# ETL_083012_59mm.net
KiCad netlist of a schematic drawn in EAGLE
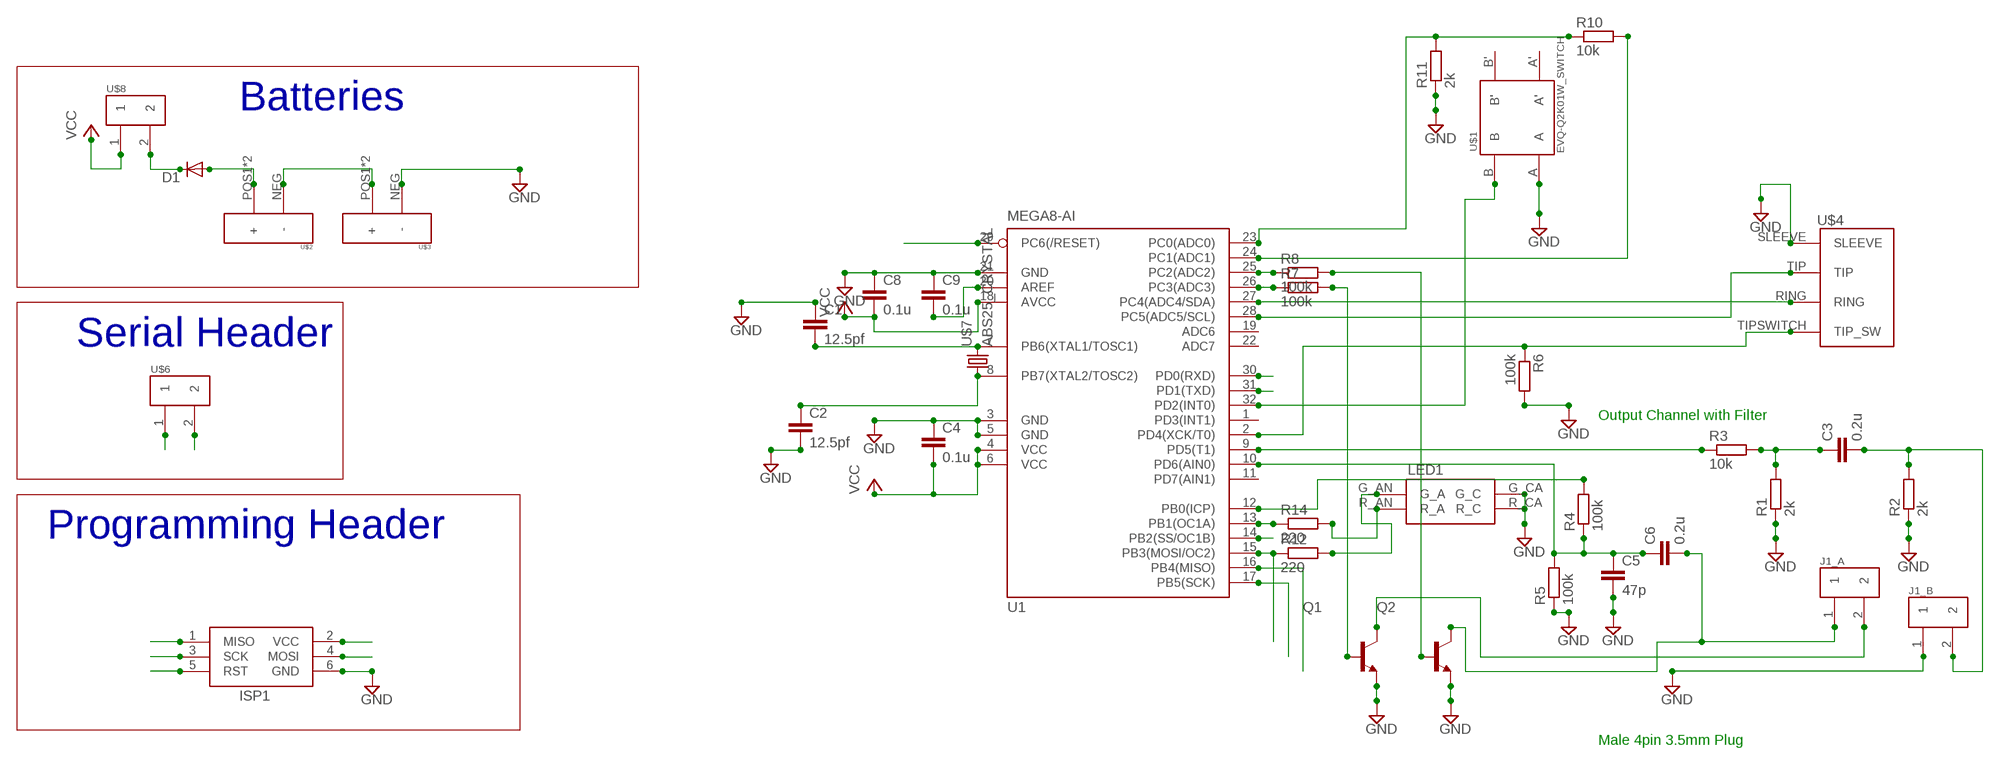
[diagram p0: schematic, sheet 1]

(export (version "E")
  (design (tool "Eeschema 10.0.6"))
  (components
    (comp (ref "C1")
      (value "12.5pf")
      (footprint "eagle-import:C0402")
      (libsource (lib "eagle-import") (part "C-EUC0402"))
    )
    (comp (ref "C2")
      (value "12.5pf")
      (footprint "eagle-import:C0402")
      (libsource (lib "eagle-import") (part "C-EUC0402"))
    )
    (comp (ref "C3")
      (value "0.2u")
      (footprint "eagle-import:C0402")
      (libsource (lib "eagle-import") (part "C-EUC0402"))
    )
    (comp (ref "C4")
      (value "0.1u")
      (footprint "eagle-import:C0402")
      (libsource (lib "eagle-import") (part "C-EUC0402"))
    )
    (comp (ref "C5")
      (value "47p")
      (footprint "eagle-import:C0402")
      (libsource (lib "eagle-import") (part "C-EUC0402"))
    )
    (comp (ref "C6")
      (value "0.2u")
      (footprint "eagle-import:C0402")
      (libsource (lib "eagle-import") (part "C-EUC0402"))
    )
    (comp (ref "C8")
      (value "0.1u")
      (footprint "eagle-import:C0402")
      (libsource (lib "eagle-import") (part "C-EUC0402"))
    )
    (comp (ref "C9")
      (value "0.1u")
      (footprint "eagle-import:C0402")
      (libsource (lib "eagle-import") (part "C-EUC0402"))
    )
    (comp (ref "D1")
      (value "DIODE-SOD323-R")
      (footprint "eagle-import:SOD323-R")
      (libsource (lib "eagle-import") (part "DIODE-SOD323-R"))
    )
    (comp (ref "ISP1")
      (value "AVRISP-6")
      (footprint "eagle-import:AVRISP")
      (libsource (lib "eagle-import") (part "AVRISP-6"))
    )
    (comp (ref "J1_A")
      (value "SERIAL_2_VERT")
      (footprint "eagle-import:SERIAL_2_VERT")
      (libsource (lib "eagle-import") (part "SERIAL_2_VERT"))
    )
    (comp (ref "J1_B")
      (value "SERIAL_2_VERT")
      (footprint "eagle-import:SERIAL_2_VERT")
      (libsource (lib "eagle-import") (part "SERIAL_2_VERT"))
    )
    (comp (ref "LED1")
      (value "LED_BI_RG")
      (footprint "eagle-import:LED_BI_1210")
      (libsource (lib "eagle-import") (part "LED_BI_RG"))
    )
    (comp (ref "Q1")
      (value "BC847-NPN-SOT23-BEC")
      (footprint "eagle-import:SOT23-BEC")
      (libsource (lib "eagle-import") (part "-NPN-SOT23-BECBC847"))
    )
    (comp (ref "Q2")
      (value "BC847-NPN-SOT23-BEC")
      (footprint "eagle-import:SOT23-BEC")
      (libsource (lib "eagle-import") (part "-NPN-SOT23-BECBC847"))
    )
    (comp (ref "R1")
      (value "2k")
      (footprint "eagle-import:R0402")
      (libsource (lib "eagle-import") (part "R-EU_R0402"))
    )
    (comp (ref "R2")
      (value "2k")
      (footprint "eagle-import:R0402")
      (libsource (lib "eagle-import") (part "R-EU_R0402"))
    )
    (comp (ref "R3")
      (value "10k")
      (footprint "eagle-import:R0402")
      (libsource (lib "eagle-import") (part "R-EU_R0402"))
    )
    (comp (ref "R4")
      (value "100k")
      (footprint "eagle-import:R0402")
      (libsource (lib "eagle-import") (part "R-EU_R0402"))
    )
    (comp (ref "R5")
      (value "100k")
      (footprint "eagle-import:R0402")
      (libsource (lib "eagle-import") (part "R-EU_R0402"))
    )
    (comp (ref "R6")
      (value "100k")
      (footprint "eagle-import:R0402")
      (libsource (lib "eagle-import") (part "R-EU_R0402"))
    )
    (comp (ref "R7")
      (value "100k")
      (footprint "eagle-import:R0402")
      (libsource (lib "eagle-import") (part "R-EU_R0402"))
    )
    (comp (ref "R8")
      (value "100k")
      (footprint "eagle-import:R0402")
      (libsource (lib "eagle-import") (part "R-EU_R0402"))
    )
    (comp (ref "R10")
      (value "10k")
      (footprint "eagle-import:R0402")
      (libsource (lib "eagle-import") (part "R-EU_R0402"))
    )
    (comp (ref "R11")
      (value "2k")
      (footprint "eagle-import:R0402")
      (libsource (lib "eagle-import") (part "R-EU_R0402"))
    )
    (comp (ref "R12")
      (value "220")
      (footprint "eagle-import:R0402")
      (libsource (lib "eagle-import") (part "R-EU_R0402"))
    )
    (comp (ref "R14")
      (value "220")
      (footprint "eagle-import:R0402")
      (libsource (lib "eagle-import") (part "R-EU_R0402"))
    )
    (comp (ref "U$1")
      (value "EVQ-Q2K01W_SWITCH")
      (footprint "eagle-import:EVQ-Q2K01W_SWITCH")
      (libsource (lib "eagle-import") (part "EVQ-Q2K01W_SWITCH"))
    )
    (comp (ref "U$2")
      (value "22M2620_BATTHOLDER")
      (footprint "eagle-import:22M2620_BATTHOLDER")
      (libsource (lib "eagle-import") (part "22M2620_BATTHOLDER"))
    )
    (comp (ref "U$3")
      (value "22M2620_BATTHOLDER")
      (footprint "eagle-import:22M2620_BATTHOLDER")
      (libsource (lib "eagle-import") (part "22M2620_BATTHOLDER"))
    )
    (comp (ref "U$4")
      (value "SJ-3524-SMT_AUDIOJACK")
      (footprint "eagle-import:SJ-3524-SMT_AUDIOJACK")
      (libsource (lib "eagle-import") (part "SJ-3524-SMT_AUDIOJACK"))
    )
    (comp (ref "U$6")
      (value "SERIAL_2_VERT")
      (footprint "eagle-import:SERIAL_2_VERT")
      (libsource (lib "eagle-import") (part "SERIAL_2_VERT"))
    )
    (comp (ref "U$7")
      (value "ABS25_CRYSTAL")
      (footprint "eagle-import:ABS25_CRYSTAL")
      (libsource (lib "eagle-import") (part "ABS25_CRYSTAL"))
    )
    (comp (ref "U$8")
      (value "SERIAL_2_VERT")
      (footprint "eagle-import:SERIAL_2_VERT")
      (libsource (lib "eagle-import") (part "SERIAL_2_VERT"))
    )
    (comp (ref "U1")
      (value "MEGA8-AI")
      (footprint "eagle-import:TQFP32-08")
      (fields (field (name "MPN") "ATMEGA8-16AU"))
      (libsource (lib "eagle-import") (part "MEGA8-AI"))
    )
  )
  (nets
    (net (code "1") (name "/MISO") (class "Default")
      (node (ref "ISP1") (pin "1") (pinfunction "MISO_1") (pintype "input"))
      (node (ref "U1") (pin "16") (pinfunction "PB4(MISO)_16") (pintype "bidirectional"))
    )
    (net (code "2") (name "/MOSI") (class "Default")
      (node (ref "ISP1") (pin "4") (pinfunction "MOSI_4") (pintype "output"))
      (node (ref "R12") (pin "1") (pinfunction "1_1") (pintype "passive"))
      (node (ref "U1") (pin "15") (pinfunction "PB3(MOSI/OC2)_15") (pintype "bidirectional"))
    )
    (net (code "3") (name "/PD0") (class "Default")
      (node (ref "U$6") (pin "1") (pinfunction "1_1") (pintype "bidirectional"))
      (node (ref "U1") (pin "30") (pinfunction "PD0(RXD)_30") (pintype "bidirectional"))
    )
    (net (code "4") (name "/PD1") (class "Default")
      (node (ref "U$6") (pin "2") (pinfunction "2_2") (pintype "bidirectional"))
      (node (ref "U1") (pin "31") (pinfunction "PD1(TXD)_31") (pintype "bidirectional"))
    )
    (net (code "5") (name "/RESET") (class "Default")
      (node (ref "ISP1") (pin "5") (pinfunction "RST_5") (pintype "output"))
      (node (ref "U1") (pin "29") (pinfunction "PC6(/RESET)_29") (pintype "bidirectional"))
    )
    (net (code "6") (name "/SCK") (class "Default")
      (node (ref "ISP1") (pin "3") (pinfunction "SCK_3") (pintype "output"))
      (node (ref "U1") (pin "17") (pinfunction "PB5(SCK)_17") (pintype "bidirectional"))
    )
    (net (code "7") (name "GND") (class "Default")
      (node (ref "C1") (pin "1") (pinfunction "1_1") (pintype "passive"))
      (node (ref "C2") (pin "2") (pinfunction "2_2") (pintype "passive"))
      (node (ref "C4") (pin "1") (pinfunction "1_1") (pintype "passive"))
      (node (ref "C5") (pin "2") (pinfunction "2_2") (pintype "passive"))
      (node (ref "C8") (pin "1") (pinfunction "1_1") (pintype "passive"))
      (node (ref "C9") (pin "1") (pinfunction "1_1") (pintype "passive"))
      (node (ref "ISP1") (pin "6") (pinfunction "GND_6") (pintype "power_in"))
      (node (ref "J1_B") (pin "1") (pinfunction "1_1") (pintype "bidirectional"))
      (node (ref "LED1") (pin "G_CA") (pinfunction "G_C_G_CA") (pintype "bidirectional"))
      (node (ref "LED1") (pin "R_CA") (pinfunction "R_C_R_CA") (pintype "bidirectional"))
      (node (ref "Q1") (pin "E") (pinfunction "E_E") (pintype "passive"))
      (node (ref "Q2") (pin "E") (pinfunction "E_E") (pintype "passive"))
      (node (ref "R1") (pin "1") (pinfunction "1_1") (pintype "passive"))
      (node (ref "R11") (pin "1") (pinfunction "1_1") (pintype "passive"))
      (node (ref "R2") (pin "1") (pinfunction "1_1") (pintype "passive"))
      (node (ref "R5") (pin "1") (pinfunction "1_1") (pintype "passive"))
      (node (ref "R6") (pin "2") (pinfunction "2_2") (pintype "passive"))
      (node (ref "U$1") (pin "A") (pinfunction "A_A") (pintype "bidirectional"))
      (node (ref "U$3") (pin "NEG") (pinfunction "-_NEG") (pintype "bidirectional"))
      (node (ref "U$4") (pin "SLEEVE") (pinfunction "SLEEVE_SLEEVE") (pintype "bidirectional"))
      (node (ref "U1") (pin "21") (pinfunction "GND_21") (pintype "power_in"))
      (node (ref "U1") (pin "3") (pinfunction "GND_3") (pintype "power_in"))
      (node (ref "U1") (pin "5") (pinfunction "GND_5") (pintype "power_in"))
    )
    (net (code "8") (name "Net-(C3-Pad1)") (class "Default")
      (node (ref "C3") (pin "1") (pinfunction "1_1") (pintype "passive"))
      (node (ref "R1") (pin "2") (pinfunction "2_2") (pintype "passive"))
      (node (ref "R3") (pin "2") (pinfunction "2_2") (pintype "passive"))
    )
    (net (code "9") (name "Net-(C3-Pad2)") (class "Default")
      (node (ref "C3") (pin "2") (pinfunction "2_2") (pintype "passive"))
      (node (ref "J1_B") (pin "2") (pinfunction "2_2") (pintype "bidirectional"))
      (node (ref "R2") (pin "2") (pinfunction "2_2") (pintype "passive"))
    )
    (net (code "10") (name "Net-(C6-Pad2)") (class "Default")
      (node (ref "C6") (pin "2") (pinfunction "2_2") (pintype "passive"))
      (node (ref "J1_A") (pin "1") (pinfunction "1_1") (pintype "bidirectional"))
      (node (ref "Q2") (pin "C") (pinfunction "C_C") (pintype "passive"))
    )
    (net (code "11") (name "Net-(D1-PadA)") (class "Default")
      (node (ref "D1") (pin "A") (pinfunction "A_A") (pintype "passive"))
      (node (ref "U$2") (pin "POS1") (pinfunction "+_POS1") (pintype "bidirectional"))
      (node (ref "U$2") (pin "POS2") (pinfunction "+_POS2") (pintype "bidirectional"))
    )
    (net (code "12") (name "Net-(D1-PadC)") (class "Default")
      (node (ref "D1") (pin "C") (pinfunction "C_C") (pintype "passive"))
      (node (ref "U$8") (pin "2") (pinfunction "2_2") (pintype "bidirectional"))
    )
    (net (code "13") (name "Net-(J1_A-Pad2)") (class "Default")
      (node (ref "J1_A") (pin "2") (pinfunction "2_2") (pintype "bidirectional"))
      (node (ref "Q1") (pin "C") (pinfunction "C_C") (pintype "passive"))
    )
    (net (code "14") (name "Net-(LED1-G_A)") (class "Default")
      (node (ref "LED1") (pin "G_AN") (pinfunction "G_A_G_AN") (pintype "bidirectional"))
      (node (ref "R12") (pin "2") (pinfunction "2_2") (pintype "passive"))
    )
    (net (code "15") (name "Net-(LED1-R_A)") (class "Default")
      (node (ref "LED1") (pin "R_AN") (pinfunction "R_A_R_AN") (pintype "bidirectional"))
      (node (ref "R14") (pin "2") (pinfunction "2_2") (pintype "passive"))
    )
    (net (code "16") (name "Net-(Q1-PadB)") (class "Default")
      (node (ref "Q1") (pin "B") (pinfunction "B_B") (pintype "passive"))
      (node (ref "R7") (pin "2") (pinfunction "2_2") (pintype "passive"))
    )
    (net (code "17") (name "Net-(Q2-PadB)") (class "Default")
      (node (ref "Q2") (pin "B") (pinfunction "B_B") (pintype "passive"))
      (node (ref "R8") (pin "2") (pinfunction "2_2") (pintype "passive"))
    )
    (net (code "18") (name "Net-(U$2--)") (class "Default")
      (node (ref "U$2") (pin "NEG") (pinfunction "-_NEG") (pintype "bidirectional"))
      (node (ref "U$3") (pin "POS1") (pinfunction "+_POS1") (pintype "bidirectional"))
      (node (ref "U$3") (pin "POS2") (pinfunction "+_POS2") (pintype "bidirectional"))
    )
    (net (code "19") (name "Net-(U$4-TIP_SW)") (class "Default")
      (node (ref "R6") (pin "1") (pinfunction "1_1") (pintype "passive"))
      (node (ref "U$4") (pin "TIPSWITCH") (pinfunction "TIP_SW_TIPSWITCH") (pintype "bidirectional"))
      (node (ref "U1") (pin "2") (pinfunction "PD4(XCK/T0)_2") (pintype "bidirectional"))
    )
    (net (code "20") (name "Net-(U$7-2)") (class "Default")
      (node (ref "C1") (pin "2") (pinfunction "2_2") (pintype "passive"))
      (node (ref "U$7") (pin "4") (pinfunction "2_4") (pintype "passive"))
      (node (ref "U1") (pin "7") (pinfunction "PB6(XTAL1/TOSC1)_7") (pintype "bidirectional"))
    )
    (net (code "21") (name "Net-(U1-AREF)") (class "Default")
      (node (ref "C9") (pin "2") (pinfunction "2_2") (pintype "passive"))
      (node (ref "U1") (pin "20") (pinfunction "AREF_20") (pintype "passive"))
    )
    (net (code "22") (name "Net-(U1-PB0(ICP))") (class "Default")
      (node (ref "R4") (pin "2") (pinfunction "2_2") (pintype "passive"))
      (node (ref "U1") (pin "12") (pinfunction "PB0(ICP)_12") (pintype "bidirectional"))
    )
    (net (code "23") (name "Net-(U1-PB1(OC1A))") (class "Default")
      (node (ref "R14") (pin "1") (pinfunction "1_1") (pintype "passive"))
      (node (ref "U1") (pin "13") (pinfunction "PB1(OC1A)_13") (pintype "bidirectional"))
    )
    (net (code "24") (name "Net-(U1-PB7(XTAL2{slash}TOSC2))") (class "Default")
      (node (ref "C2") (pin "1") (pinfunction "1_1") (pintype "passive"))
      (node (ref "U$7") (pin "1") (pinfunction "1_1") (pintype "passive"))
      (node (ref "U1") (pin "8") (pinfunction "PB7(XTAL2/TOSC2)_8") (pintype "bidirectional"))
    )
    (net (code "25") (name "Net-(U1-PC0(ADC0))") (class "Default")
      (node (ref "R10") (pin "1") (pinfunction "1_1") (pintype "passive"))
      (node (ref "R11") (pin "2") (pinfunction "2_2") (pintype "passive"))
      (node (ref "U1") (pin "23") (pinfunction "PC0(ADC0)_23") (pintype "bidirectional"))
    )
    (net (code "26") (name "Net-(U1-PC1(ADC1))") (class "Default")
      (node (ref "R10") (pin "2") (pinfunction "2_2") (pintype "passive"))
      (node (ref "U1") (pin "24") (pinfunction "PC1(ADC1)_24") (pintype "bidirectional"))
    )
    (net (code "27") (name "Net-(U1-PC2(ADC2))") (class "Default")
      (node (ref "R8") (pin "1") (pinfunction "1_1") (pintype "passive"))
      (node (ref "U1") (pin "25") (pinfunction "PC2(ADC2)_25") (pintype "bidirectional"))
    )
    (net (code "28") (name "Net-(U1-PC3(ADC3))") (class "Default")
      (node (ref "R7") (pin "1") (pinfunction "1_1") (pintype "passive"))
      (node (ref "U1") (pin "26") (pinfunction "PC3(ADC3)_26") (pintype "bidirectional"))
    )
    (net (code "29") (name "Net-(U1-PC4(ADC4{slash}SDA))") (class "Default")
      (node (ref "U$4") (pin "RING") (pinfunction "RING_RING") (pintype "bidirectional"))
      (node (ref "U1") (pin "27") (pinfunction "PC4(ADC4/SDA)_27") (pintype "bidirectional"))
    )
    (net (code "30") (name "Net-(U1-PC5(ADC5{slash}SCL))") (class "Default")
      (node (ref "U$4") (pin "TIP") (pinfunction "TIP_TIP") (pintype "bidirectional"))
      (node (ref "U1") (pin "28") (pinfunction "PC5(ADC5/SCL)_28") (pintype "bidirectional"))
    )
    (net (code "31") (name "Net-(U1-PD2(INT0))") (class "Default")
      (node (ref "U$1") (pin "B") (pinfunction "B_B") (pintype "bidirectional"))
      (node (ref "U1") (pin "32") (pinfunction "PD2(INT0)_32") (pintype "bidirectional"))
    )
    (net (code "32") (name "Net-(U1-PD5(T1))") (class "Default")
      (node (ref "R3") (pin "1") (pinfunction "1_1") (pintype "passive"))
      (node (ref "U1") (pin "9") (pinfunction "PD5(T1)_9") (pintype "bidirectional"))
    )
    (net (code "33") (name "Net-(U1-PD6(AIN0))") (class "Default")
      (node (ref "C5") (pin "1") (pinfunction "1_1") (pintype "passive"))
      (node (ref "C6") (pin "1") (pinfunction "1_1") (pintype "passive"))
      (node (ref "R4") (pin "1") (pinfunction "1_1") (pintype "passive"))
      (node (ref "R5") (pin "2") (pinfunction "2_2") (pintype "passive"))
      (node (ref "U1") (pin "10") (pinfunction "PD6(AIN0)_10") (pintype "bidirectional"))
    )
    (net (code "34") (name "VCC") (class "Default")
      (node (ref "C4") (pin "2") (pinfunction "2_2") (pintype "passive"))
      (node (ref "C8") (pin "2") (pinfunction "2_2") (pintype "passive"))
      (node (ref "ISP1") (pin "2") (pinfunction "VCC_2") (pintype "power_in"))
      (node (ref "U$8") (pin "1") (pinfunction "1_1") (pintype "bidirectional"))
      (node (ref "U1") (pin "18") (pinfunction "AVCC_18") (pintype "power_in"))
      (node (ref "U1") (pin "4") (pinfunction "VCC_4") (pintype "power_in"))
      (node (ref "U1") (pin "6") (pinfunction "VCC_6") (pintype "power_in"))
    )
    (net (code "35") (name "unconnected-(U$1-PadA')") (class "Default")
      (node (ref "U$1") (pin "A'") (pinfunction "A'_A'") (pintype "bidirectional"))
    )
    (net (code "36") (name "unconnected-(U$1-PadB')") (class "Default")
      (node (ref "U$1") (pin "B'") (pinfunction "B'_B'") (pintype "bidirectional"))
    )
    (net (code "37") (name "unconnected-(U1-ADC6-Pad19)") (class "Default")
      (node (ref "U1") (pin "19") (pinfunction "ADC6_19") (pintype "bidirectional"))
    )
    (net (code "38") (name "unconnected-(U1-ADC7-Pad22)") (class "Default")
      (node (ref "U1") (pin "22") (pinfunction "ADC7_22") (pintype "bidirectional"))
    )
    (net (code "39") (name "unconnected-(U1-PB2(SS{slash}OC1B)-Pad14)") (class "Default")
      (node (ref "U1") (pin "14") (pinfunction "PB2(SS/OC1B)_14") (pintype "bidirectional"))
    )
    (net (code "40") (name "unconnected-(U1-PD3(INT1)-Pad1)") (class "Default")
      (node (ref "U1") (pin "1") (pinfunction "PD3(INT1)_1") (pintype "bidirectional"))
    )
    (net (code "41") (name "unconnected-(U1-PD7(AIN1)-Pad11)") (class "Default")
      (node (ref "U1") (pin "11") (pinfunction "PD7(AIN1)_11") (pintype "bidirectional"))
    )
  )
)
